# transmitterArduinoHat.net
KiCad netlist of a schematic drawn in EAGLE
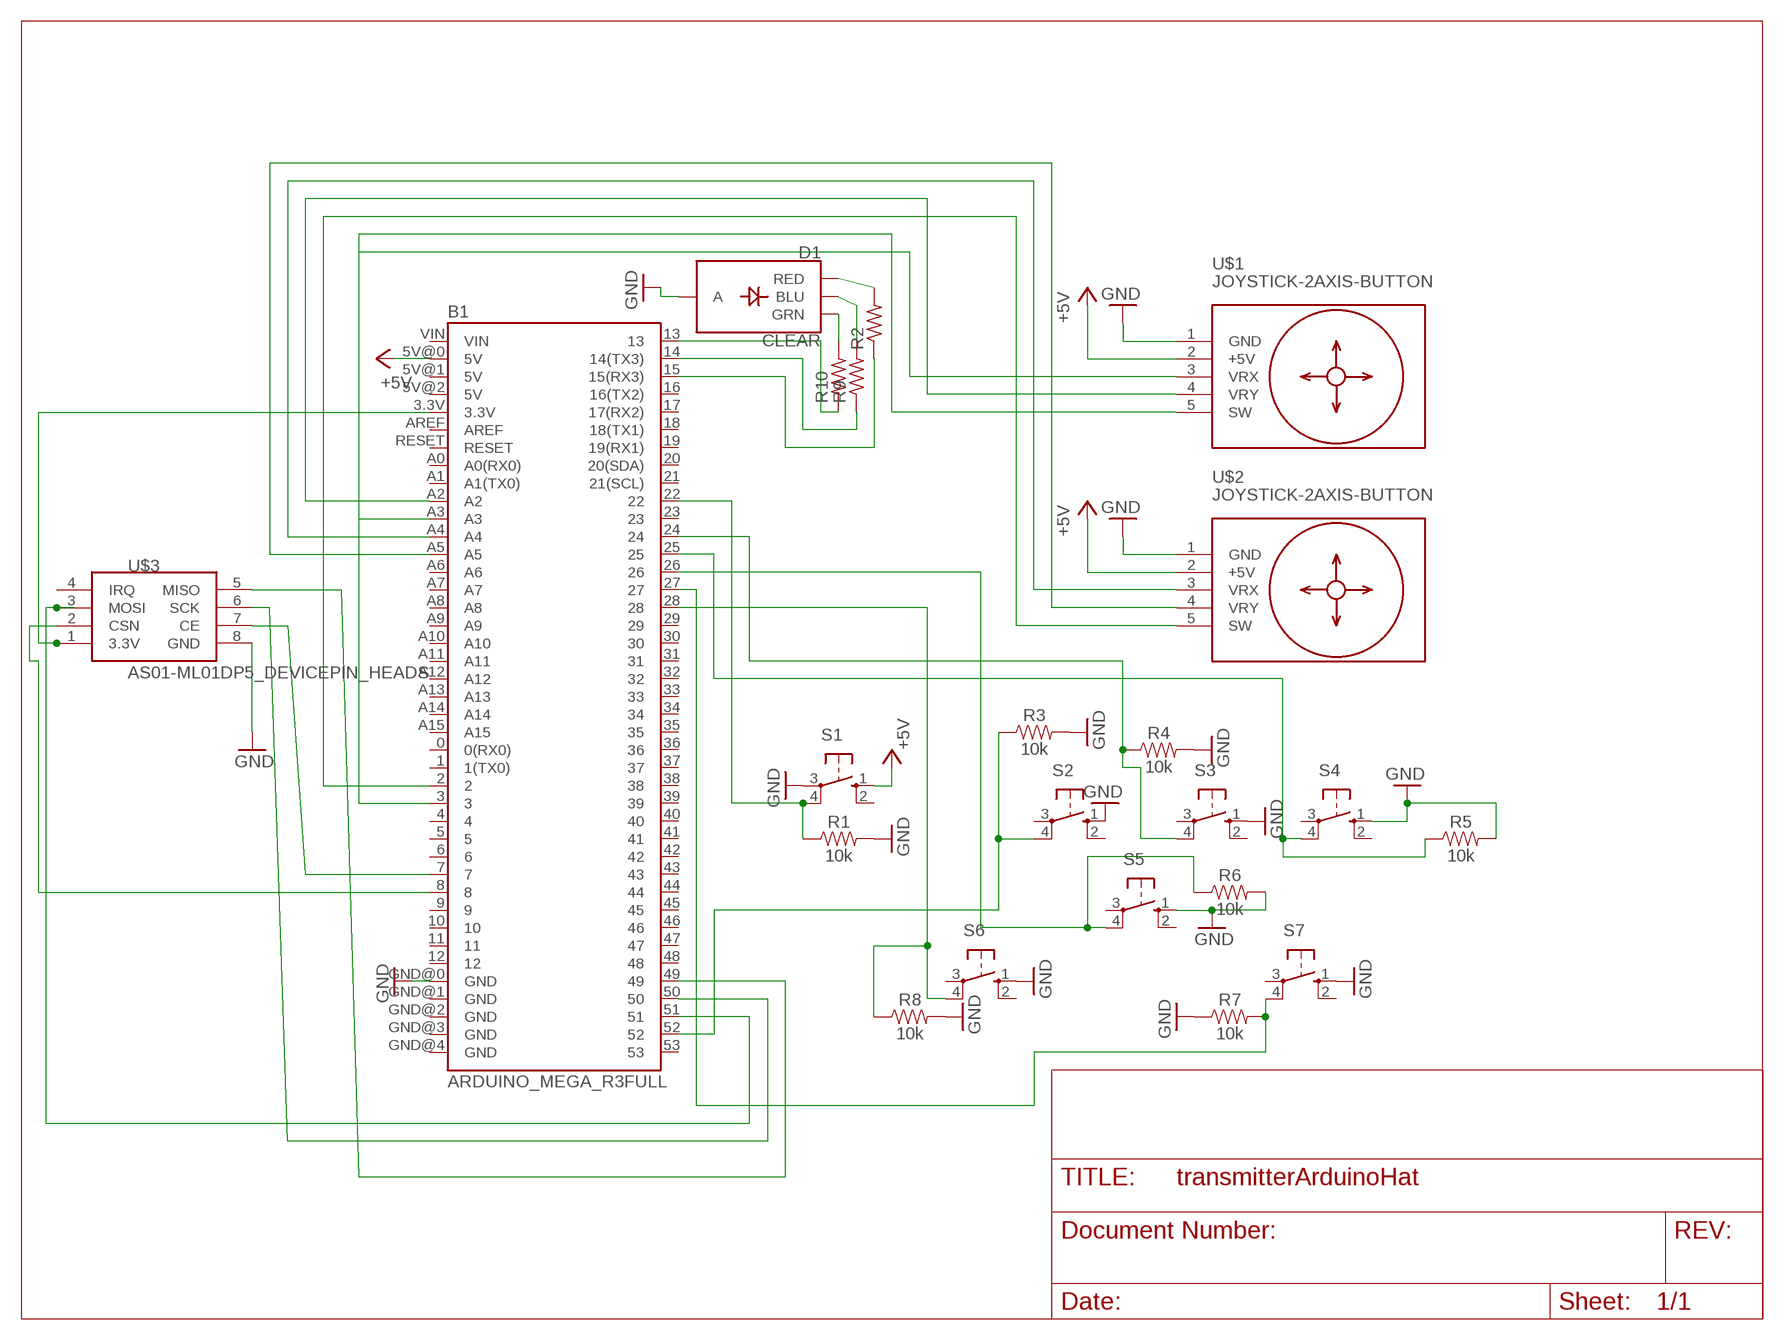
[diagram p0: schematic, sheet 1]

(export (version "E")
  (design (tool "Eeschema 10.0.6"))
  (components
    (comp (ref "B1")
      (value "ARDUINO_MEGA_R3FULL")
      (footprint "eagle-import:ARDUINO_MEGA")
      (libsource (lib "eagle-import") (part "ARDUINO_MEGA_R3FULL"))
    )
    (comp (ref "D1")
      (value "CLEAR")
      (footprint "eagle-import:LED-RGB-THRU")
      (libsource (lib "eagle-import") (part "LED-RGB-CACLEAR"))
    )
    (comp (ref "R1")
      (value "10k")
      (footprint "eagle-import:AXIAL-0.1")
      (libsource (lib "eagle-import") (part "10KOHM-VERT-1/4W-1%"))
    )
    (comp (ref "R2")
      (value "R-US_V234/12")
      (footprint "eagle-import:V234_12")
      (libsource (lib "eagle-import") (part "R-US_V234/12"))
    )
    (comp (ref "R3")
      (value "10k")
      (footprint "eagle-import:AXIAL-0.1")
      (libsource (lib "eagle-import") (part "10KOHM-VERT-1/4W-1%"))
    )
    (comp (ref "R4")
      (value "10k")
      (footprint "eagle-import:AXIAL-0.1")
      (libsource (lib "eagle-import") (part "10KOHM-VERT-1/4W-1%"))
    )
    (comp (ref "R5")
      (value "10k")
      (footprint "eagle-import:AXIAL-0.1")
      (libsource (lib "eagle-import") (part "10KOHM-VERT-1/4W-1%"))
    )
    (comp (ref "R6")
      (value "10k")
      (footprint "eagle-import:AXIAL-0.1")
      (libsource (lib "eagle-import") (part "10KOHM-VERT-1/4W-1%"))
    )
    (comp (ref "R7")
      (value "10k")
      (footprint "eagle-import:AXIAL-0.1")
      (libsource (lib "eagle-import") (part "10KOHM-VERT-1/4W-1%"))
    )
    (comp (ref "R8")
      (value "10k")
      (footprint "eagle-import:AXIAL-0.1")
      (libsource (lib "eagle-import") (part "10KOHM-VERT-1/4W-1%"))
    )
    (comp (ref "R9")
      (value "R-US_V234/12")
      (footprint "eagle-import:V234_12")
      (libsource (lib "eagle-import") (part "R-US_V234/12"))
    )
    (comp (ref "R10")
      (value "R-US_V234/12")
      (footprint "eagle-import:V234_12")
      (libsource (lib "eagle-import") (part "R-US_V234/12"))
    )
    (comp (ref "S1")
      (value "10-XX")
      (footprint "eagle-import:B3F-10XX")
      (fields (field (name "MPN") "B3F-1000"))
      (libsource (lib "eagle-import") (part "10-XX"))
    )
    (comp (ref "S2")
      (value "10-XX")
      (footprint "eagle-import:B3F-10XX")
      (fields (field (name "MPN") "B3F-1000"))
      (libsource (lib "eagle-import") (part "10-XX"))
    )
    (comp (ref "S3")
      (value "10-XX")
      (footprint "eagle-import:B3F-10XX")
      (fields (field (name "MPN") "B3F-1000"))
      (libsource (lib "eagle-import") (part "10-XX"))
    )
    (comp (ref "S4")
      (value "10-XX")
      (footprint "eagle-import:B3F-10XX")
      (fields (field (name "MPN") "B3F-1000"))
      (libsource (lib "eagle-import") (part "10-XX"))
    )
    (comp (ref "S5")
      (value "10-XX")
      (footprint "eagle-import:B3F-10XX")
      (fields (field (name "MPN") "B3F-1000"))
      (libsource (lib "eagle-import") (part "10-XX"))
    )
    (comp (ref "S6")
      (value "10-XX")
      (footprint "eagle-import:B3F-10XX")
      (fields (field (name "MPN") "B3F-1000"))
      (libsource (lib "eagle-import") (part "10-XX"))
    )
    (comp (ref "S7")
      (value "10-XX")
      (footprint "eagle-import:B3F-10XX")
      (fields (field (name "MPN") "B3F-1000"))
      (libsource (lib "eagle-import") (part "10-XX"))
    )
    (comp (ref "U$1")
      (value "JOYSTICK-2AXIS-BUTTON")
      (footprint "eagle-import:JOYSTICK-2AXIS-BUTTON")
      (libsource (lib "eagle-import") (part "JOYSTICK-2AXIS-BUTTON"))
    )
    (comp (ref "U$2")
      (value "JOYSTICK-2AXIS-BUTTON")
      (footprint "eagle-import:JOYSTICK-2AXIS-BUTTON")
      (libsource (lib "eagle-import") (part "JOYSTICK-2AXIS-BUTTON"))
    )
    (comp (ref "U$3")
      (value "AS01-ML01DP5_DEVICEPIN_HEADS")
      (footprint "eagle-import:HDRV8W64P254_2X4_1016X508X838B")
      (libsource (lib "eagle-import") (part "AS01-ML01DP5_DEVICEPIN_HEADS"))
    )
  )
  (nets
    (net (code "1") (name "+5V") (class "Default")
      (node (ref "B1") (pin "5V@0") (pinfunction "5V_5V@0") (pintype "bidirectional"))
      (node (ref "S1") (pin "1") (pinfunction "S_1") (pintype "passive"))
      (node (ref "U$1") (pin "2") (pinfunction "+5V_2") (pintype "power_in"))
      (node (ref "U$2") (pin "2") (pinfunction "+5V_2") (pintype "power_in"))
    )
    (net (code "2") (name "GND") (class "Default")
      (node (ref "B1") (pin "GND@0") (pinfunction "GND_GND@0") (pintype "bidirectional"))
      (node (ref "D1") (pin "2") (pinfunction "A_2") (pintype "bidirectional"))
      (node (ref "R1") (pin "P$2") (pinfunction "2_P$2") (pintype "passive"))
      (node (ref "R3") (pin "P$2") (pinfunction "2_P$2") (pintype "passive"))
      (node (ref "R4") (pin "P$2") (pinfunction "2_P$2") (pintype "passive"))
      (node (ref "R5") (pin "P$2") (pinfunction "2_P$2") (pintype "passive"))
      (node (ref "R6") (pin "P$2") (pinfunction "2_P$2") (pintype "passive"))
      (node (ref "R7") (pin "P$1") (pinfunction "1_P$1") (pintype "passive"))
      (node (ref "R8") (pin "P$2") (pinfunction "2_P$2") (pintype "passive"))
      (node (ref "S1") (pin "3") (pinfunction "P_3") (pintype "passive"))
      (node (ref "S2") (pin "1") (pinfunction "S_1") (pintype "passive"))
      (node (ref "S3") (pin "1") (pinfunction "S_1") (pintype "passive"))
      (node (ref "S4") (pin "1") (pinfunction "S_1") (pintype "passive"))
      (node (ref "S5") (pin "1") (pinfunction "S_1") (pintype "passive"))
      (node (ref "S6") (pin "1") (pinfunction "S_1") (pintype "passive"))
      (node (ref "S7") (pin "1") (pinfunction "S_1") (pintype "passive"))
      (node (ref "U$1") (pin "1") (pinfunction "GND_1") (pintype "power_in"))
      (node (ref "U$2") (pin "1") (pinfunction "GND_1") (pintype "power_in"))
      (node (ref "U$3") (pin "8") (pinfunction "GND_8") (pintype "bidirectional"))
    )
    (net (code "3") (name "Net-(B1-14(TX3))") (class "Default")
      (node (ref "B1") (pin "14") (pinfunction "14(TX3)_14") (pintype "bidirectional"))
      (node (ref "R9") (pin "1") (pinfunction "1_1") (pintype "passive"))
    )
    (net (code "4") (name "Net-(B1-15(RX3))") (class "Default")
      (node (ref "B1") (pin "15") (pinfunction "15(RX3)_15") (pintype "bidirectional"))
      (node (ref "R2") (pin "1") (pinfunction "1_1") (pintype "passive"))
    )
    (net (code "5") (name "Net-(B1-Pad13)") (class "Default")
      (node (ref "B1") (pin "13") (pinfunction "13_13") (pintype "bidirectional"))
      (node (ref "R10") (pin "1") (pinfunction "1_1") (pintype "passive"))
    )
    (net (code "6") (name "Net-(D1-BLU)") (class "Default")
      (node (ref "D1") (pin "4") (pinfunction "BLU_4") (pintype "bidirectional"))
      (node (ref "R9") (pin "2") (pinfunction "2_2") (pintype "passive"))
    )
    (net (code "7") (name "Net-(D1-GRN)") (class "Default")
      (node (ref "D1") (pin "3") (pinfunction "GRN_3") (pintype "bidirectional"))
      (node (ref "R10") (pin "2") (pinfunction "2_2") (pintype "passive"))
    )
    (net (code "8") (name "Net-(D1-RED)") (class "Default")
      (node (ref "D1") (pin "1") (pinfunction "RED_1") (pintype "bidirectional"))
      (node (ref "R2") (pin "2") (pinfunction "2_2") (pintype "passive"))
    )
    (net (code "9") (name "Net-(R1-1)") (class "Default")
      (node (ref "B1") (pin "22") (pinfunction "22_22") (pintype "bidirectional"))
      (node (ref "R1") (pin "P$1") (pinfunction "1_P$1") (pintype "passive"))
      (node (ref "S1") (pin "4") (pinfunction "P1_4") (pintype "passive"))
    )
    (net (code "10") (name "Net-(R3-1)") (class "Default")
      (node (ref "B1") (pin "52") (pinfunction "52_52") (pintype "bidirectional"))
      (node (ref "R3") (pin "P$1") (pinfunction "1_P$1") (pintype "passive"))
      (node (ref "S2") (pin "4") (pinfunction "P1_4") (pintype "passive"))
    )
    (net (code "11") (name "Net-(R4-1)") (class "Default")
      (node (ref "B1") (pin "24") (pinfunction "24_24") (pintype "bidirectional"))
      (node (ref "R4") (pin "P$1") (pinfunction "1_P$1") (pintype "passive"))
      (node (ref "S3") (pin "4") (pinfunction "P1_4") (pintype "passive"))
    )
    (net (code "12") (name "Net-(R5-1)") (class "Default")
      (node (ref "B1") (pin "25") (pinfunction "25_25") (pintype "bidirectional"))
      (node (ref "R5") (pin "P$1") (pinfunction "1_P$1") (pintype "passive"))
      (node (ref "S4") (pin "4") (pinfunction "P1_4") (pintype "passive"))
    )
    (net (code "13") (name "Net-(R6-1)") (class "Default")
      (node (ref "B1") (pin "26") (pinfunction "26_26") (pintype "bidirectional"))
      (node (ref "R6") (pin "P$1") (pinfunction "1_P$1") (pintype "passive"))
      (node (ref "S5") (pin "4") (pinfunction "P1_4") (pintype "passive"))
    )
    (net (code "14") (name "Net-(R7-2)") (class "Default")
      (node (ref "B1") (pin "27") (pinfunction "27_27") (pintype "bidirectional"))
      (node (ref "R7") (pin "P$2") (pinfunction "2_P$2") (pintype "passive"))
      (node (ref "S7") (pin "4") (pinfunction "P1_4") (pintype "passive"))
    )
    (net (code "15") (name "Net-(R8-1)") (class "Default")
      (node (ref "B1") (pin "28") (pinfunction "28_28") (pintype "bidirectional"))
      (node (ref "R8") (pin "P$1") (pinfunction "1_P$1") (pintype "passive"))
      (node (ref "S6") (pin "4") (pinfunction "P1_4") (pintype "passive"))
    )
    (net (code "16") (name "Net-(U$1-SW)") (class "Default")
      (node (ref "B1") (pin "3") (pinfunction "3_3") (pintype "bidirectional"))
      (node (ref "U$1") (pin "5") (pinfunction "SW_5") (pintype "passive"))
    )
    (net (code "17") (name "Net-(U$1-VRX)") (class "Default")
      (node (ref "B1") (pin "A3") (pinfunction "A3_A3") (pintype "bidirectional"))
      (node (ref "U$1") (pin "3") (pinfunction "VRX_3") (pintype "passive"))
    )
    (net (code "18") (name "Net-(U$1-VRY)") (class "Default")
      (node (ref "B1") (pin "A2") (pinfunction "A2_A2") (pintype "bidirectional"))
      (node (ref "U$1") (pin "4") (pinfunction "VRY_4") (pintype "passive"))
    )
    (net (code "19") (name "Net-(U$2-SW)") (class "Default")
      (node (ref "B1") (pin "2") (pinfunction "2_2") (pintype "bidirectional"))
      (node (ref "U$2") (pin "5") (pinfunction "SW_5") (pintype "passive"))
    )
    (net (code "20") (name "Net-(U$2-VRX)") (class "Default")
      (node (ref "B1") (pin "A4") (pinfunction "A4_A4") (pintype "bidirectional"))
      (node (ref "U$2") (pin "3") (pinfunction "VRX_3") (pintype "passive"))
    )
    (net (code "21") (name "Net-(U$2-VRY)") (class "Default")
      (node (ref "B1") (pin "A5") (pinfunction "A5_A5") (pintype "bidirectional"))
      (node (ref "U$2") (pin "4") (pinfunction "VRY_4") (pintype "passive"))
    )
    (net (code "22") (name "Net-(U$3-3.3V)") (class "Default")
      (node (ref "B1") (pin "3.3V") (pinfunction "3.3V_3.3V") (pintype "bidirectional"))
      (node (ref "U$3") (pin "1") (pinfunction "3.3V_1") (pintype "bidirectional"))
    )
    (net (code "23") (name "Net-(U$3-CE)") (class "Default")
      (node (ref "B1") (pin "7") (pinfunction "7_7") (pintype "bidirectional"))
      (node (ref "U$3") (pin "7") (pinfunction "CE_7") (pintype "bidirectional"))
    )
    (net (code "24") (name "Net-(U$3-CSN)") (class "Default")
      (node (ref "B1") (pin "8") (pinfunction "8_8") (pintype "bidirectional"))
      (node (ref "U$3") (pin "2") (pinfunction "CSN_2") (pintype "bidirectional"))
    )
    (net (code "25") (name "Net-(U$3-MISO)") (class "Default")
      (node (ref "B1") (pin "49") (pinfunction "49_49") (pintype "bidirectional"))
      (node (ref "U$3") (pin "5") (pinfunction "MISO_5") (pintype "bidirectional"))
    )
    (net (code "26") (name "Net-(U$3-MOSI)") (class "Default")
      (node (ref "B1") (pin "51") (pinfunction "51_51") (pintype "bidirectional"))
      (node (ref "U$3") (pin "3") (pinfunction "MOSI_3") (pintype "bidirectional"))
    )
    (net (code "27") (name "Net-(U$3-SCK)") (class "Default")
      (node (ref "B1") (pin "50") (pinfunction "50_50") (pintype "bidirectional"))
      (node (ref "U$3") (pin "6") (pinfunction "SCK_6") (pintype "bidirectional"))
    )
    (net (code "28") (name "unconnected-(B1-0(RX0)-Pad0)") (class "Default")
      (node (ref "B1") (pin "0") (pinfunction "0(RX0)_0") (pintype "bidirectional"))
    )
    (net (code "29") (name "unconnected-(B1-1(TX0)-Pad1)") (class "Default")
      (node (ref "B1") (pin "1") (pinfunction "1(TX0)_1") (pintype "bidirectional"))
    )
    (net (code "30") (name "unconnected-(B1-5V-Pad5V@1)") (class "Default")
      (node (ref "B1") (pin "5V@1") (pinfunction "5V_5V@1") (pintype "bidirectional"))
    )
    (net (code "31") (name "unconnected-(B1-5V-Pad5V@2)") (class "Default")
      (node (ref "B1") (pin "5V@2") (pinfunction "5V_5V@2") (pintype "bidirectional"))
    )
    (net (code "32") (name "unconnected-(B1-16(TX2)-Pad16)") (class "Default")
      (node (ref "B1") (pin "16") (pinfunction "16(TX2)_16") (pintype "bidirectional"))
    )
    (net (code "33") (name "unconnected-(B1-17(RX2)-Pad17)") (class "Default")
      (node (ref "B1") (pin "17") (pinfunction "17(RX2)_17") (pintype "bidirectional"))
    )
    (net (code "34") (name "unconnected-(B1-18(TX1)-Pad18)") (class "Default")
      (node (ref "B1") (pin "18") (pinfunction "18(TX1)_18") (pintype "bidirectional"))
    )
    (net (code "35") (name "unconnected-(B1-19(RX1)-Pad19)") (class "Default")
      (node (ref "B1") (pin "19") (pinfunction "19(RX1)_19") (pintype "bidirectional"))
    )
    (net (code "36") (name "unconnected-(B1-20(SDA)-Pad20)") (class "Default")
      (node (ref "B1") (pin "20") (pinfunction "20(SDA)_20") (pintype "bidirectional"))
    )
    (net (code "37") (name "unconnected-(B1-21(SCL)-Pad21)") (class "Default")
      (node (ref "B1") (pin "21") (pinfunction "21(SCL)_21") (pintype "bidirectional"))
    )
    (net (code "38") (name "unconnected-(B1-A0(RX0)-PadA0)") (class "Default")
      (node (ref "B1") (pin "A0") (pinfunction "A0(RX0)_A0") (pintype "bidirectional"))
    )
    (net (code "39") (name "unconnected-(B1-A1(TX0)-PadA1)") (class "Default")
      (node (ref "B1") (pin "A1") (pinfunction "A1(TX0)_A1") (pintype "bidirectional"))
    )
    (net (code "40") (name "unconnected-(B1-GND-PadGND@1)") (class "Default")
      (node (ref "B1") (pin "GND@1") (pinfunction "GND_GND@1") (pintype "bidirectional"))
    )
    (net (code "41") (name "unconnected-(B1-GND-PadGND@2)") (class "Default")
      (node (ref "B1") (pin "GND@2") (pinfunction "GND_GND@2") (pintype "bidirectional"))
    )
    (net (code "42") (name "unconnected-(B1-GND-PadGND@3)") (class "Default")
      (node (ref "B1") (pin "GND@3") (pinfunction "GND_GND@3") (pintype "bidirectional"))
    )
    (net (code "43") (name "unconnected-(B1-GND-PadGND@4)") (class "Default")
      (node (ref "B1") (pin "GND@4") (pinfunction "GND_GND@4") (pintype "bidirectional"))
    )
    (net (code "44") (name "unconnected-(B1-Pad4)") (class "Default")
      (node (ref "B1") (pin "4") (pinfunction "4_4") (pintype "bidirectional"))
    )
    (net (code "45") (name "unconnected-(B1-Pad5)") (class "Default")
      (node (ref "B1") (pin "5") (pinfunction "5_5") (pintype "bidirectional"))
    )
    (net (code "46") (name "unconnected-(B1-Pad6)") (class "Default")
      (node (ref "B1") (pin "6") (pinfunction "6_6") (pintype "bidirectional"))
    )
    (net (code "47") (name "unconnected-(B1-Pad9)") (class "Default")
      (node (ref "B1") (pin "9") (pinfunction "9_9") (pintype "bidirectional"))
    )
    (net (code "48") (name "unconnected-(B1-Pad10)") (class "Default")
      (node (ref "B1") (pin "10") (pinfunction "10_10") (pintype "bidirectional"))
    )
    (net (code "49") (name "unconnected-(B1-Pad11)") (class "Default")
      (node (ref "B1") (pin "11") (pinfunction "11_11") (pintype "bidirectional"))
    )
    (net (code "50") (name "unconnected-(B1-Pad12)") (class "Default")
      (node (ref "B1") (pin "12") (pinfunction "12_12") (pintype "bidirectional"))
    )
    (net (code "51") (name "unconnected-(B1-Pad23)") (class "Default")
      (node (ref "B1") (pin "23") (pinfunction "23_23") (pintype "bidirectional"))
    )
    (net (code "52") (name "unconnected-(B1-Pad29)") (class "Default")
      (node (ref "B1") (pin "29") (pinfunction "29_29") (pintype "bidirectional"))
    )
    (net (code "53") (name "unconnected-(B1-Pad30)") (class "Default")
      (node (ref "B1") (pin "30") (pinfunction "30_30") (pintype "bidirectional"))
    )
    (net (code "54") (name "unconnected-(B1-Pad31)") (class "Default")
      (node (ref "B1") (pin "31") (pinfunction "31_31") (pintype "bidirectional"))
    )
    (net (code "55") (name "unconnected-(B1-Pad32)") (class "Default")
      (node (ref "B1") (pin "32") (pinfunction "32_32") (pintype "bidirectional"))
    )
    (net (code "56") (name "unconnected-(B1-Pad33)") (class "Default")
      (node (ref "B1") (pin "33") (pinfunction "33_33") (pintype "bidirectional"))
    )
    (net (code "57") (name "unconnected-(B1-Pad34)") (class "Default")
      (node (ref "B1") (pin "34") (pinfunction "34_34") (pintype "bidirectional"))
    )
    (net (code "58") (name "unconnected-(B1-Pad35)") (class "Default")
      (node (ref "B1") (pin "35") (pinfunction "35_35") (pintype "bidirectional"))
    )
    (net (code "59") (name "unconnected-(B1-Pad36)") (class "Default")
      (node (ref "B1") (pin "36") (pinfunction "36_36") (pintype "bidirectional"))
    )
    (net (code "60") (name "unconnected-(B1-Pad37)") (class "Default")
      (node (ref "B1") (pin "37") (pinfunction "37_37") (pintype "bidirectional"))
    )
    (net (code "61") (name "unconnected-(B1-Pad38)") (class "Default")
      (node (ref "B1") (pin "38") (pinfunction "38_38") (pintype "bidirectional"))
    )
    (net (code "62") (name "unconnected-(B1-Pad39)") (class "Default")
      (node (ref "B1") (pin "39") (pinfunction "39_39") (pintype "bidirectional"))
    )
    (net (code "63") (name "unconnected-(B1-Pad40)") (class "Default")
      (node (ref "B1") (pin "40") (pinfunction "40_40") (pintype "bidirectional"))
    )
    (net (code "64") (name "unconnected-(B1-Pad41)") (class "Default")
      (node (ref "B1") (pin "41") (pinfunction "41_41") (pintype "bidirectional"))
    )
    (net (code "65") (name "unconnected-(B1-Pad42)") (class "Default")
      (node (ref "B1") (pin "42") (pinfunction "42_42") (pintype "bidirectional"))
    )
    (net (code "66") (name "unconnected-(B1-Pad43)") (class "Default")
      (node (ref "B1") (pin "43") (pinfunction "43_43") (pintype "bidirectional"))
    )
    (net (code "67") (name "unconnected-(B1-Pad44)") (class "Default")
      (node (ref "B1") (pin "44") (pinfunction "44_44") (pintype "bidirectional"))
    )
    (net (code "68") (name "unconnected-(B1-Pad45)") (class "Default")
      (node (ref "B1") (pin "45") (pinfunction "45_45") (pintype "bidirectional"))
    )
    (net (code "69") (name "unconnected-(B1-Pad46)") (class "Default")
      (node (ref "B1") (pin "46") (pinfunction "46_46") (pintype "bidirectional"))
    )
    (net (code "70") (name "unconnected-(B1-Pad47)") (class "Default")
      (node (ref "B1") (pin "47") (pinfunction "47_47") (pintype "bidirectional"))
    )
    (net (code "71") (name "unconnected-(B1-Pad48)") (class "Default")
      (node (ref "B1") (pin "48") (pinfunction "48_48") (pintype "bidirectional"))
    )
    (net (code "72") (name "unconnected-(B1-Pad53)") (class "Default")
      (node (ref "B1") (pin "53") (pinfunction "53_53") (pintype "bidirectional"))
    )
    (net (code "73") (name "unconnected-(B1-PadA6)") (class "Default")
      (node (ref "B1") (pin "A6") (pinfunction "A6_A6") (pintype "bidirectional"))
    )
    (net (code "74") (name "unconnected-(B1-PadA7)") (class "Default")
      (node (ref "B1") (pin "A7") (pinfunction "A7_A7") (pintype "bidirectional"))
    )
    (net (code "75") (name "unconnected-(B1-PadA8)") (class "Default")
      (node (ref "B1") (pin "A8") (pinfunction "A8_A8") (pintype "bidirectional"))
    )
    (net (code "76") (name "unconnected-(B1-PadA9)") (class "Default")
      (node (ref "B1") (pin "A9") (pinfunction "A9_A9") (pintype "bidirectional"))
    )
    (net (code "77") (name "unconnected-(B1-PadA10)") (class "Default")
      (node (ref "B1") (pin "A10") (pinfunction "A10_A10") (pintype "bidirectional"))
    )
    (net (code "78") (name "unconnected-(B1-PadA11)") (class "Default")
      (node (ref "B1") (pin "A11") (pinfunction "A11_A11") (pintype "bidirectional"))
    )
    (net (code "79") (name "unconnected-(B1-PadA12)") (class "Default")
      (node (ref "B1") (pin "A12") (pinfunction "A12_A12") (pintype "bidirectional"))
    )
    (net (code "80") (name "unconnected-(B1-PadA13)") (class "Default")
      (node (ref "B1") (pin "A13") (pinfunction "A13_A13") (pintype "bidirectional"))
    )
    (net (code "81") (name "unconnected-(B1-PadA14)") (class "Default")
      (node (ref "B1") (pin "A14") (pinfunction "A14_A14") (pintype "bidirectional"))
    )
    (net (code "82") (name "unconnected-(B1-PadA15)") (class "Default")
      (node (ref "B1") (pin "A15") (pinfunction "A15_A15") (pintype "bidirectional"))
    )
    (net (code "83") (name "unconnected-(B1-PadAREF)") (class "Default")
      (node (ref "B1") (pin "AREF") (pinfunction "AREF_AREF") (pintype "bidirectional"))
    )
    (net (code "84") (name "unconnected-(B1-PadRESET)") (class "Default")
      (node (ref "B1") (pin "RESET") (pinfunction "RESET_RESET") (pintype "bidirectional"))
    )
    (net (code "85") (name "unconnected-(B1-PadVIN)") (class "Default")
      (node (ref "B1") (pin "VIN") (pinfunction "VIN_VIN") (pintype "bidirectional"))
    )
    (net (code "86") (name "unconnected-(S1-S1-Pad2)") (class "Default")
      (node (ref "S1") (pin "2") (pinfunction "S1_2") (pintype "passive"))
    )
    (net (code "87") (name "unconnected-(S2-P-Pad3)") (class "Default")
      (node (ref "S2") (pin "3") (pinfunction "P_3") (pintype "passive"))
    )
    (net (code "88") (name "unconnected-(S2-S1-Pad2)") (class "Default")
      (node (ref "S2") (pin "2") (pinfunction "S1_2") (pintype "passive"))
    )
    (net (code "89") (name "unconnected-(S3-P-Pad3)") (class "Default")
      (node (ref "S3") (pin "3") (pinfunction "P_3") (pintype "passive"))
    )
    (net (code "90") (name "unconnected-(S3-S1-Pad2)") (class "Default")
      (node (ref "S3") (pin "2") (pinfunction "S1_2") (pintype "passive"))
    )
    (net (code "91") (name "unconnected-(S4-P-Pad3)") (class "Default")
      (node (ref "S4") (pin "3") (pinfunction "P_3") (pintype "passive"))
    )
    (net (code "92") (name "unconnected-(S4-S1-Pad2)") (class "Default")
      (node (ref "S4") (pin "2") (pinfunction "S1_2") (pintype "passive"))
    )
    (net (code "93") (name "unconnected-(S5-P-Pad3)") (class "Default")
      (node (ref "S5") (pin "3") (pinfunction "P_3") (pintype "passive"))
    )
    (net (code "94") (name "unconnected-(S5-S1-Pad2)") (class "Default")
      (node (ref "S5") (pin "2") (pinfunction "S1_2") (pintype "passive"))
    )
    (net (code "95") (name "unconnected-(S6-P-Pad3)") (class "Default")
      (node (ref "S6") (pin "3") (pinfunction "P_3") (pintype "passive"))
    )
    (net (code "96") (name "unconnected-(S6-S1-Pad2)") (class "Default")
      (node (ref "S6") (pin "2") (pinfunction "S1_2") (pintype "passive"))
    )
    (net (code "97") (name "unconnected-(S7-P-Pad3)") (class "Default")
      (node (ref "S7") (pin "3") (pinfunction "P_3") (pintype "passive"))
    )
    (net (code "98") (name "unconnected-(S7-S1-Pad2)") (class "Default")
      (node (ref "S7") (pin "2") (pinfunction "S1_2") (pintype "passive"))
    )
    (net (code "99") (name "unconnected-(U$3-IRQ-Pad4)") (class "Default")
      (node (ref "U$3") (pin "4") (pinfunction "IRQ_4") (pintype "bidirectional"))
    )
  )
)
